# ID3.net
KiCad netlist of a schematic drawn in Altium Designer
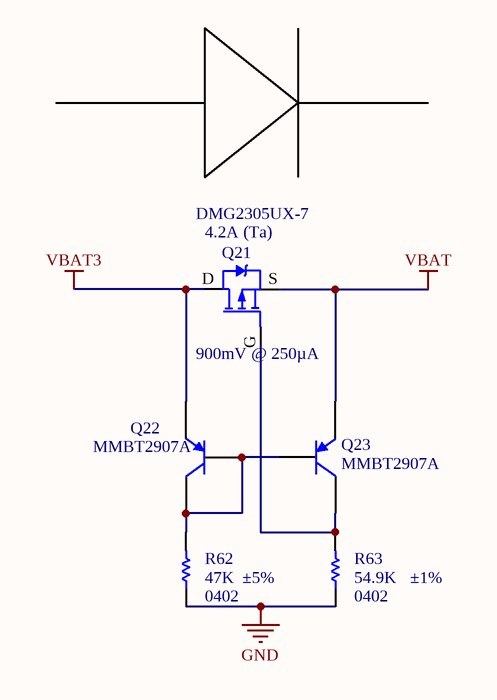
[diagram p0: ID3.SchDoc]

(export (version "E")
  (design (tool "Eeschema 10.0.6"))
  (components
    (comp (ref "Q21")
      (value "DMG2305UX")
      (footprint "DMG2305UX-7")
      (description "MOSFET P-CH 20V 4.2A SOT23")
      (fields
        (field (name "MANUFACTURER") "Diodes Incorporated")
        (field (name "CURRENT - CONTINUOUS DRAIN (ID) @ 25°C") "4.2A (Ta)")
        (field (name "VGS(TH) (MAX) @ ID") "900mV @ 250µA")
        (field (name "MANUFACTURER PART NUMBER") "DMG2305UX-7")
        (field (name "CREATOR") "osman")
      )
      (libsource (lib "OLogic-Trans-Drivers") (part "DMG2305UX"))
    )
    (comp (ref "Q22")
      (value "MMBT2907A")
      (footprint "SOT23")
      (description "PNP General Purpose Amplifier")
      (fields (field (name "MANUFACTURER") "Fairchild Semiconductor"))
      (libsource (lib "OLogic-Trans-Drivers") (part "MMBT2907A"))
    )
    (comp (ref "Q23")
      (value "MMBT2907A")
      (footprint "SOT23")
      (description "PNP General Purpose Amplifier")
      (fields (field (name "MANUFACTURER") "Fairchild Semiconductor"))
      (libsource (lib "OLogic-Trans-Drivers") (part "MMBT2907A"))
    )
    (comp (ref "R62")
      (value "47K")
      (footprint "RESC0402(1005)_N")
      (description "47K 0402")
      (fields
        (field (name "MANUFACTURER") "Panasonic Electronic Components")
        (field (name "MANUFACTURER PART NUMBER") "ERJ-2GEJ473X")
        (field (name "TOLERANCE") "±5%")
        (field (name "SUPPLIER DEVICE PACKAGE") "0402")
      )
      (libsource (lib "OLogic-Passive") (part "RES 47K OHM 5% 1/10W 0402"))
    )
    (comp (ref "R63")
      (value "54.9K")
      (footprint "RESC0402(1005)_N")
      (description "54.9K 1% 0402")
      (fields
        (field (name "MANUFACTURER") "Panasonic Electronic Components")
        (field (name "MANUFACTURER PART NUMBER") "ERJ-2RKF5492X")
        (field (name "TOLERANCE") "±1%")
        (field (name "SUPPLIER DEVICE PACKAGE") "0402")
      )
      (libsource (lib "OLogic-Passive") (part "RES 54.9K OHM 1% 1/10W 0402"))
    )
  )
  (nets
    (net (code "1") (name "GND") (class "Default")
      (node (ref "R62") (pin "1") (pinfunction "1_1") (pintype "passive"))
      (node (ref "R63") (pin "1") (pinfunction "1_1") (pintype "passive"))
    )
    (net (code "2") (name "Net-(Q22-B)") (class "Default")
      (node (ref "Q22") (pin "1") (pinfunction "B_1") (pintype "passive"))
      (node (ref "Q22") (pin "3") (pinfunction "C_3") (pintype "passive"))
      (node (ref "Q23") (pin "1") (pinfunction "B_1") (pintype "passive"))
      (node (ref "R62") (pin "2") (pinfunction "2_2") (pintype "passive"))
    )
    (net (code "3") (name "Net-(Q23-C)") (class "Default")
      (node (ref "Q21") (pin "G") (pinfunction "G_G") (pintype "passive"))
      (node (ref "Q23") (pin "3") (pinfunction "C_3") (pintype "passive"))
      (node (ref "R63") (pin "2") (pinfunction "2_2") (pintype "passive"))
    )
    (net (code "4") (name "VBAT") (class "Default")
      (node (ref "Q21") (pin "S") (pinfunction "S_S") (pintype "passive"))
      (node (ref "Q23") (pin "2") (pinfunction "E_2") (pintype "passive"))
    )
    (net (code "5") (name "VBAT3") (class "Default")
      (node (ref "Q21") (pin "D") (pinfunction "D_D") (pintype "passive"))
      (node (ref "Q22") (pin "2") (pinfunction "E_2") (pintype "passive"))
    )
  )
)
